# Mainboard_RMII_Header_Connector.net
KiCad netlist of a schematic drawn in Altium Designer
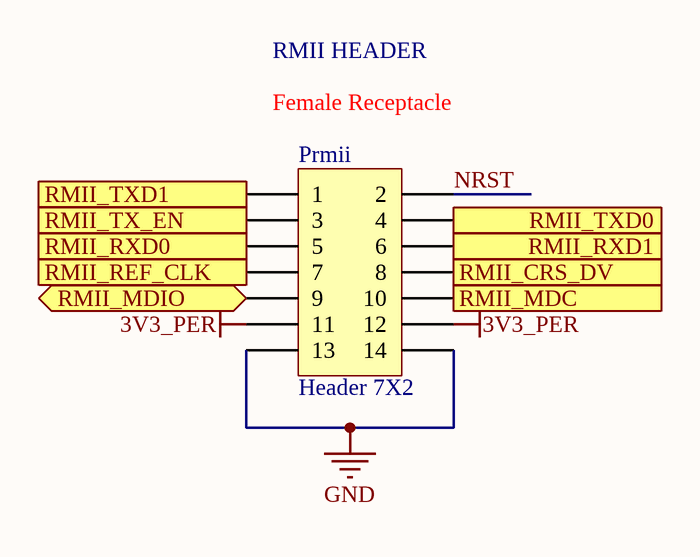
[diagram p0: Mainboard_RMII Header Connector.SchDoc]

(export (version "E")
  (design (tool "Eeschema 10.0.6"))
  (components
    (comp (ref "Prmii")
      (value "Header 7X2")
      (footprint "HDR2X7")
      (description "Header, 7-Pin, Dual row")
      (fields (field (name "PUBLISHER") "Altium Limited"))
      (libsource (lib "Miscellaneous Connectors") (part "Header 7X2"))
    )
  )
  (nets
    (net (code "1") (name "/NRST") (class "Default")
      (node (ref "Prmii") (pin "2") (pinfunction "2_2") (pintype "passive"))
    )
    (net (code "2") (name "/RMII_CRS_DV") (class "Default")
      (node (ref "Prmii") (pin "8") (pinfunction "8_8") (pintype "passive"))
    )
    (net (code "3") (name "/RMII_MDC") (class "Default")
      (node (ref "Prmii") (pin "10") (pinfunction "10_10") (pintype "passive"))
    )
    (net (code "4") (name "/RMII_MDIO") (class "Default")
      (node (ref "Prmii") (pin "9") (pinfunction "9_9") (pintype "passive"))
    )
    (net (code "5") (name "/RMII_REF_CLK") (class "Default")
      (node (ref "Prmii") (pin "7") (pinfunction "7_7") (pintype "passive"))
    )
    (net (code "6") (name "/RMII_RXD0") (class "Default")
      (node (ref "Prmii") (pin "5") (pinfunction "5_5") (pintype "passive"))
    )
    (net (code "7") (name "/RMII_RXD1") (class "Default")
      (node (ref "Prmii") (pin "6") (pinfunction "6_6") (pintype "passive"))
    )
    (net (code "8") (name "/RMII_TXD0") (class "Default")
      (node (ref "Prmii") (pin "4") (pinfunction "4_4") (pintype "passive"))
    )
    (net (code "9") (name "/RMII_TXD1") (class "Default")
      (node (ref "Prmii") (pin "1") (pinfunction "1_1") (pintype "passive"))
    )
    (net (code "10") (name "/RMII_TX_EN") (class "Default")
      (node (ref "Prmii") (pin "3") (pinfunction "3_3") (pintype "passive"))
    )
    (net (code "11") (name "3V3_PER") (class "Default")
      (node (ref "Prmii") (pin "11") (pinfunction "11_11") (pintype "passive"))
      (node (ref "Prmii") (pin "12") (pinfunction "12_12") (pintype "passive"))
    )
    (net (code "12") (name "GND") (class "Default")
      (node (ref "Prmii") (pin "13") (pinfunction "13_13") (pintype "passive"))
      (node (ref "Prmii") (pin "14") (pinfunction "14_14") (pintype "passive"))
    )
  )
)
